# 325V-Gleichstrom-Motor-an-Phasenanschnit.net
KiCad netlist of a schematic drawn in EAGLE
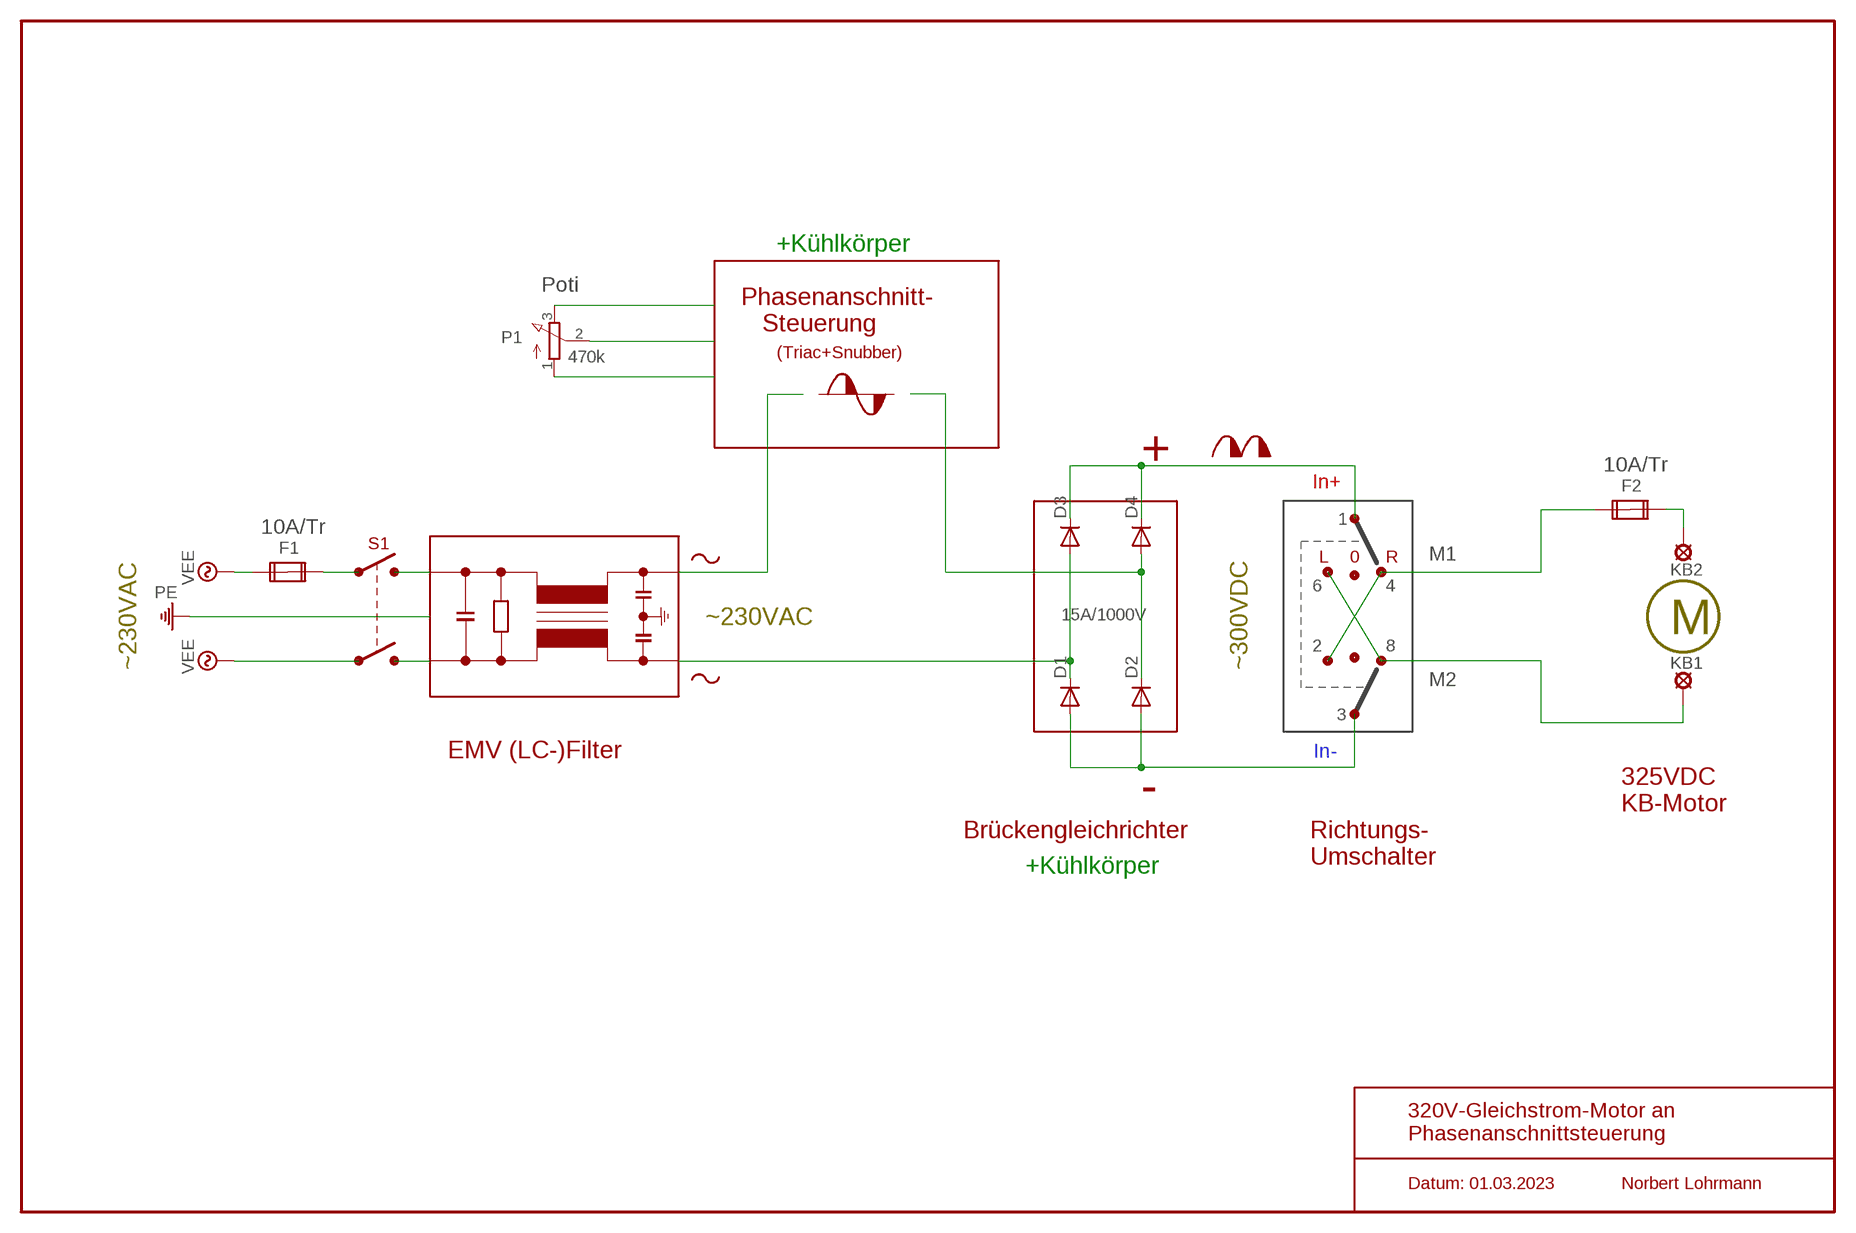
[diagram p0: schematic, sheet 1]

(export (version "E")
  (design (tool "Eeschema 10.0.6"))
  (components
    (comp (ref "D1")
      (value "DIODE-D-2.5")
      (footprint "eagle-import:D-2.5")
      (libsource (lib "eagle-import") (part "DIODE-D-2.5"))
    )
    (comp (ref "D2")
      (value "DIODE-D-2.5")
      (footprint "eagle-import:D-2.5")
      (libsource (lib "eagle-import") (part "DIODE-D-2.5"))
    )
    (comp (ref "D3")
      (value "DIODE-D-2.5")
      (footprint "eagle-import:D-2.5")
      (libsource (lib "eagle-import") (part "DIODE-D-2.5"))
    )
    (comp (ref "D4")
      (value "DIODE-D-2.5")
      (footprint "eagle-import:D-2.5")
      (libsource (lib "eagle-import") (part "DIODE-D-2.5"))
    )
    (comp (ref "F1")
      (value "10A/Tr")
      (footprint "eagle-import:FUSE1")
      (libsource (lib "eagle-import") (part "FUSE2P"))
    )
    (comp (ref "F2")
      (value "10A/Tr")
      (footprint "eagle-import:FUSE1")
      (libsource (lib "eagle-import") (part "FUSE2P"))
    )
    (comp (ref "KB1")
      (value "LSP10")
      (footprint "eagle-import:LSP10")
      (libsource (lib "eagle-import") (part "LSP10"))
    )
    (comp (ref "KB2")
      (value "LSP10")
      (footprint "eagle-import:LSP10")
      (libsource (lib "eagle-import") (part "LSP10"))
    )
    (comp (ref "P1")
      (value "Poti")
      (footprint "eagle-import:3RP_1610N")
      (libsource (lib "eagle-import") (part "3RP/1610N"))
    )
  )
  (nets
    (net (code "1") (name "Net-(D1-PadA)") (class "Default")
      (node (ref "D1") (pin "A") (pinfunction "A_A") (pintype "passive"))
      (node (ref "D2") (pin "A") (pinfunction "A_A") (pintype "passive"))
    )
    (net (code "2") (name "Net-(D1-PadC)") (class "Default")
      (node (ref "D1") (pin "C") (pinfunction "C_C") (pintype "passive"))
      (node (ref "D3") (pin "A") (pinfunction "A_A") (pintype "passive"))
    )
    (net (code "3") (name "Net-(D2-PadC)") (class "Default")
      (node (ref "D2") (pin "C") (pinfunction "C_C") (pintype "passive"))
      (node (ref "D4") (pin "A") (pinfunction "A_A") (pintype "passive"))
    )
    (net (code "4") (name "Net-(D3-PadC)") (class "Default")
      (node (ref "D3") (pin "C") (pinfunction "C_C") (pintype "passive"))
      (node (ref "D4") (pin "C") (pinfunction "C_C") (pintype "passive"))
    )
    (net (code "5") (name "Net-(F2-Pad2A)") (class "Default")
      (node (ref "F2") (pin "2A") (pinfunction "2A_2A") (pintype "passive"))
      (node (ref "KB2") (pin "MP") (pinfunction "MP_MP") (pintype "passive"))
    )
    (net (code "7") (name "VEE") (class "Default")
      (node (ref "F1") (pin "1A") (pinfunction "1A_1A") (pintype "passive"))
    )
    (net (code "8") (name "unconnected-(F1-Pad1B)") (class "Default")
      (node (ref "F1") (pin "1B") (pinfunction "1B_1B") (pintype "passive"))
    )
    (net (code "9") (name "unconnected-(F1-Pad2A)") (class "Default")
      (node (ref "F1") (pin "2A") (pinfunction "2A_2A") (pintype "passive"))
    )
    (net (code "10") (name "unconnected-(F1-Pad2B)") (class "Default")
      (node (ref "F1") (pin "2B") (pinfunction "2B_2B") (pintype "passive"))
    )
    (net (code "11") (name "unconnected-(F2-Pad1A)") (class "Default")
      (node (ref "F2") (pin "1A") (pinfunction "1A_1A") (pintype "passive"))
    )
    (net (code "12") (name "unconnected-(F2-Pad1B)") (class "Default")
      (node (ref "F2") (pin "1B") (pinfunction "1B_1B") (pintype "passive"))
    )
    (net (code "13") (name "unconnected-(F2-Pad2B)") (class "Default")
      (node (ref "F2") (pin "2B") (pinfunction "2B_2B") (pintype "passive"))
    )
    (net (code "14") (name "unconnected-(KB1-PadMP)") (class "Default")
      (node (ref "KB1") (pin "MP") (pinfunction "MP_MP") (pintype "passive"))
    )
    (net (code "15") (name "unconnected-(P1-A-Pad1)") (class "Default")
      (node (ref "P1") (pin "1") (pinfunction "A_1") (pintype "passive"))
    )
    (net (code "16") (name "unconnected-(P1-E-Pad3)") (class "Default")
      (node (ref "P1") (pin "3") (pinfunction "E_3") (pintype "passive"))
    )
    (net (code "17") (name "unconnected-(P1-S-Pad2)") (class "Default")
      (node (ref "P1") (pin "2") (pinfunction "S_2") (pintype "passive"))
    )
  )
)
